# p0tx-001.net
KiCad netlist of a schematic drawn in EAGLE
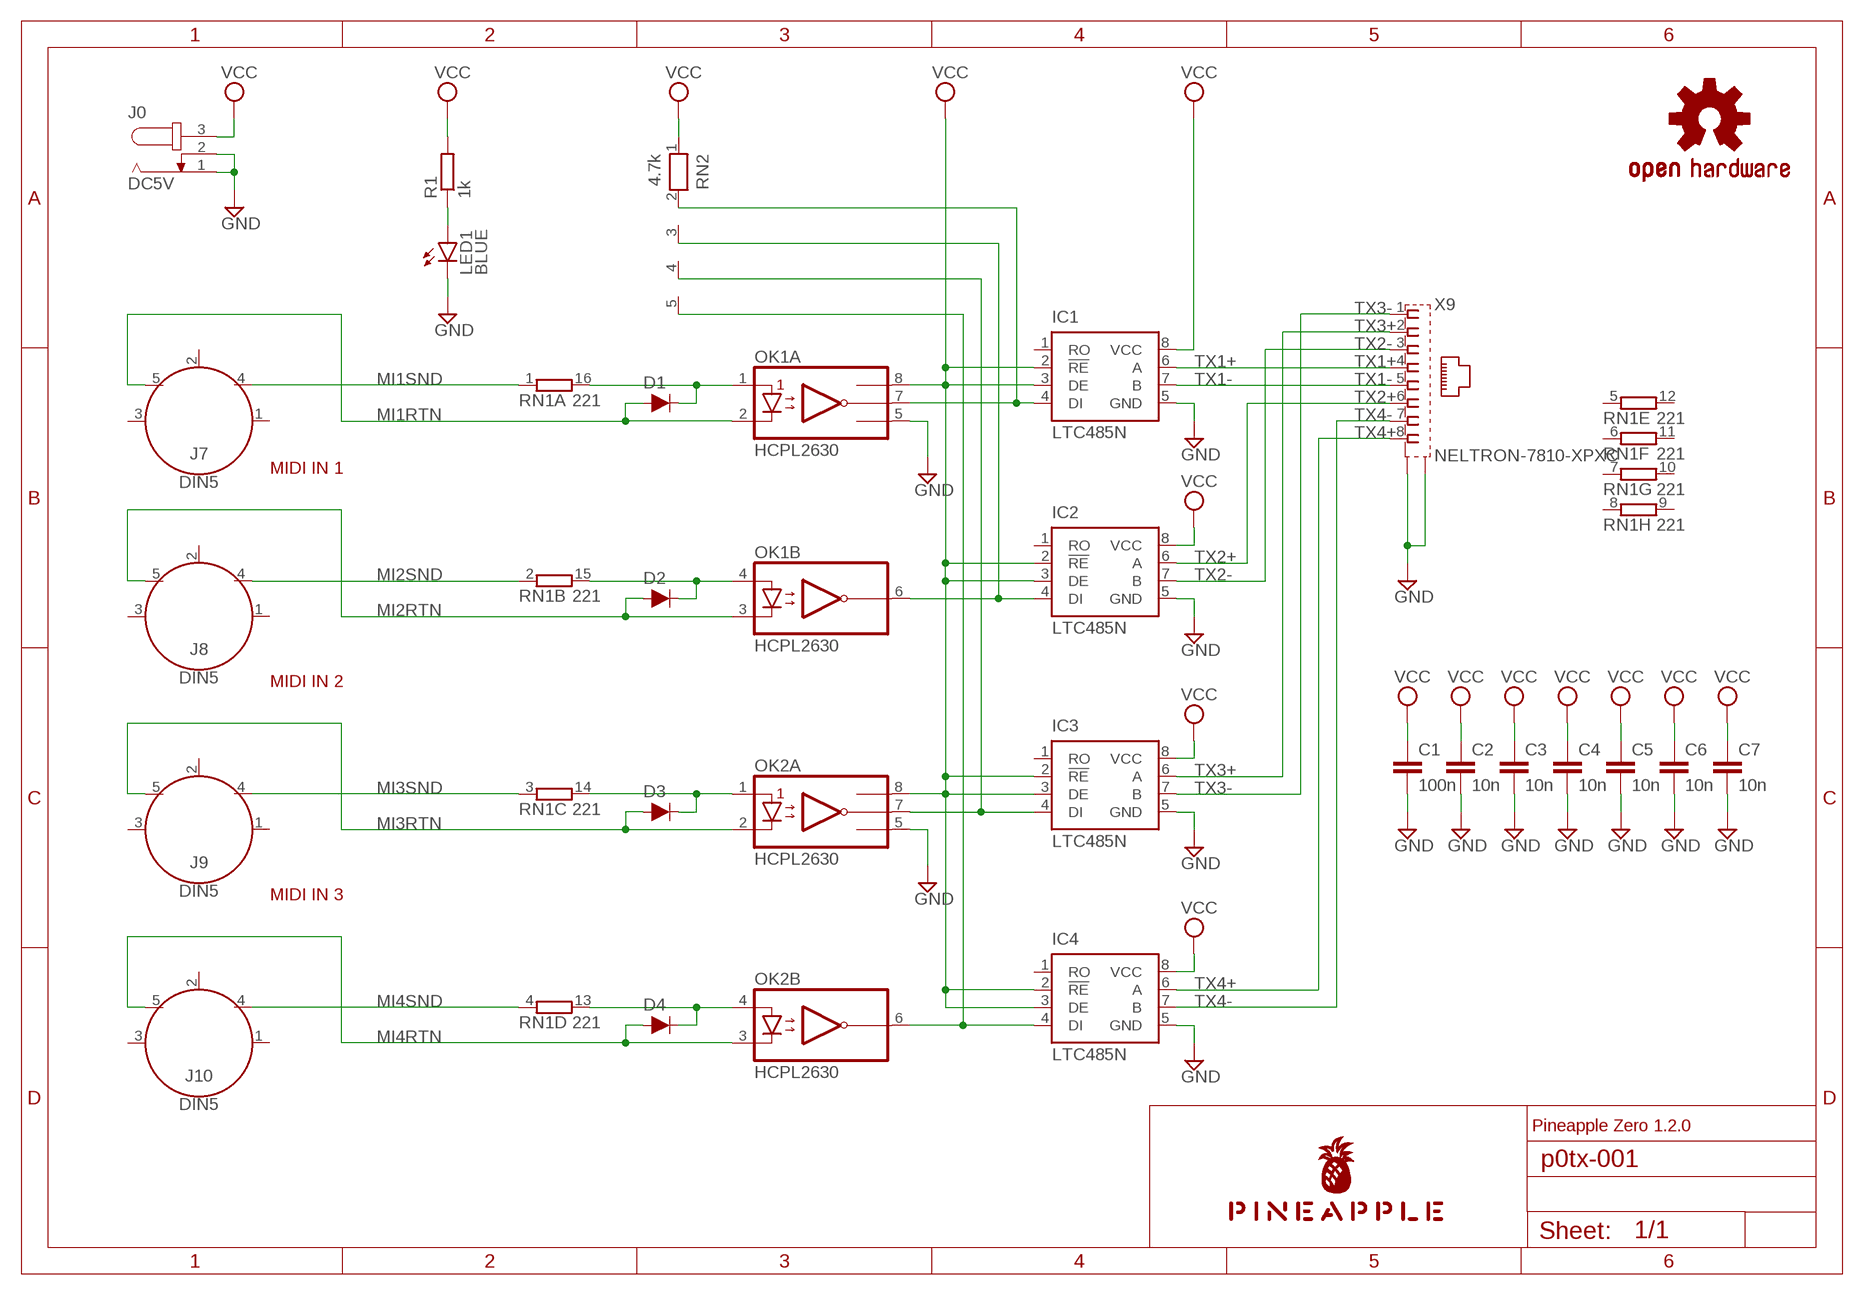
[diagram p0: schematic, sheet 1]

(export (version "E")
  (design (tool "Eeschema 10.0.6"))
  (components
    (comp (ref "C1")
      (value "100n")
      (footprint "eagle-import:C025-024X044")
      (libsource (lib "eagle-import") (part "C-EU025-024X044"))
    )
    (comp (ref "C2")
      (value "10n")
      (footprint "eagle-import:C025-024X044")
      (libsource (lib "eagle-import") (part "C-EU025-024X044"))
    )
    (comp (ref "C3")
      (value "10n")
      (footprint "eagle-import:C025-024X044")
      (libsource (lib "eagle-import") (part "C-EU025-024X044"))
    )
    (comp (ref "C4")
      (value "10n")
      (footprint "eagle-import:C025-024X044")
      (libsource (lib "eagle-import") (part "C-EU025-024X044"))
    )
    (comp (ref "C5")
      (value "10n")
      (footprint "eagle-import:C025-024X044")
      (libsource (lib "eagle-import") (part "C-EU025-024X044"))
    )
    (comp (ref "C6")
      (value "10n")
      (footprint "eagle-import:C025-024X044")
      (libsource (lib "eagle-import") (part "C-EU025-024X044"))
    )
    (comp (ref "C7")
      (value "10n")
      (footprint "eagle-import:C025-024X044")
      (libsource (lib "eagle-import") (part "C-EU025-024X044"))
    )
    (comp (ref "D1")
      (value "DIODE-1N4148")
      (footprint "eagle-import:DIODE-1N4148")
      (libsource (lib "eagle-import") (part "DIODE-1N4148"))
    )
    (comp (ref "D2")
      (value "DIODE-1N4148")
      (footprint "eagle-import:DIODE-1N4148")
      (libsource (lib "eagle-import") (part "DIODE-1N4148"))
    )
    (comp (ref "D3")
      (value "DIODE-1N4148")
      (footprint "eagle-import:DIODE-1N4148")
      (libsource (lib "eagle-import") (part "DIODE-1N4148"))
    )
    (comp (ref "D4")
      (value "DIODE-1N4148")
      (footprint "eagle-import:DIODE-1N4148")
      (libsource (lib "eagle-import") (part "DIODE-1N4148"))
    )
    (comp (ref "IC1")
      (value "LTC485N")
      (footprint "eagle-import:DIL08")
      (libsource (lib "eagle-import") (part "LTC485N"))
    )
    (comp (ref "IC2")
      (value "LTC485N")
      (footprint "eagle-import:DIL08")
      (libsource (lib "eagle-import") (part "LTC485N"))
    )
    (comp (ref "IC3")
      (value "LTC485N")
      (footprint "eagle-import:DIL08")
      (libsource (lib "eagle-import") (part "LTC485N"))
    )
    (comp (ref "IC4")
      (value "LTC485N")
      (footprint "eagle-import:DIL08")
      (libsource (lib "eagle-import") (part "LTC485N"))
    )
    (comp (ref "J0")
      (value "DC5V")
      (footprint "eagle-import:SPC4077")
      (libsource (lib "eagle-import") (part "JACK-PLUG0"))
    )
    (comp (ref "J7")
      (value "DIN5")
      (footprint "eagle-import:DIN5-RA-PTH")
      (libsource (lib "eagle-import") (part "DIN5"))
    )
    (comp (ref "J8")
      (value "DIN5")
      (footprint "eagle-import:DIN5-RA-PTH")
      (libsource (lib "eagle-import") (part "DIN5"))
    )
    (comp (ref "J9")
      (value "DIN5")
      (footprint "eagle-import:DIN5-RA-PTH")
      (libsource (lib "eagle-import") (part "DIN5"))
    )
    (comp (ref "J10")
      (value "DIN5")
      (footprint "eagle-import:DIN5-RA-PTH")
      (libsource (lib "eagle-import") (part "DIN5"))
    )
    (comp (ref "LED1")
      (value "BLUE")
      (footprint "eagle-import:LED3MM")
      (libsource (lib "eagle-import") (part "LED3MM"))
    )
    (comp (ref "LOGO1")
      (value "OSHW-LOGOS-COPPER")
      (footprint "eagle-import:OSHW-LOGO-S_COPPER")
      (libsource (lib "eagle-import") (part "OSHW-LOGOS-COPPER"))
    )
    (comp (ref "OK1")
      (value "HCPL2630")
      (footprint "eagle-import:DIL08")
      (fields (field (name "MF") "AGILENT TECHNOLOGIES") (field (name "MPN") "HCPL-2630-000E"))
      (libsource (lib "eagle-import") (part "HCPL2630"))
    )
    (comp (ref "OK2")
      (value "HCPL2630")
      (footprint "eagle-import:DIL08")
      (fields (field (name "MF") "AGILENT TECHNOLOGIES") (field (name "MPN") "HCPL-2630-000E"))
      (libsource (lib "eagle-import") (part "HCPL2630"))
    )
    (comp (ref "R1")
      (value "1k")
      (footprint "eagle-import:0204_5")
      (libsource (lib "eagle-import") (part "R-EU_0204/5"))
    )
    (comp (ref "RN1")
      (value "221")
      (footprint "eagle-import:DIL16")
      (libsource (lib "eagle-import") (part "8R-N"))
    )
    (comp (ref "RN2")
      (value "4.7k")
      (footprint "eagle-import:RN-5")
      (libsource (lib "eagle-import") (part "RN04"))
    )
    (comp (ref "U$1")
      (value "PINEAPPLE450")
      (footprint "eagle-import:PINEAPPLE450")
      (libsource (lib "eagle-import") (part "PINEAPPLE450"))
    )
    (comp (ref "X9")
      (value "NELTRON-7810-XPXC")
      (footprint "eagle-import:NELTRON-7810-XPXC-FOOTPRINT")
      (libsource (lib "eagle-import") (part "NELTRON-7810-XPXC"))
    )
  )
  (nets
    (net (code "1") (name "/MI1RTN") (class "Default")
      (node (ref "D1") (pin "A") (pinfunction "A_A") (pintype "passive"))
      (node (ref "J7") (pin "5") (pinfunction "5_5") (pintype "bidirectional"))
      (node (ref "OK1") (pin "2") (pinfunction "C1_2") (pintype "passive"))
    )
    (net (code "2") (name "/MI1SND") (class "Default")
      (node (ref "J7") (pin "4") (pinfunction "4_4") (pintype "bidirectional"))
      (node (ref "RN1") (pin "1") (pinfunction "1_1") (pintype "passive"))
    )
    (net (code "3") (name "/MI2RTN") (class "Default")
      (node (ref "D2") (pin "A") (pinfunction "A_A") (pintype "passive"))
      (node (ref "J8") (pin "5") (pinfunction "5_5") (pintype "bidirectional"))
      (node (ref "OK1") (pin "3") (pinfunction "C2_3") (pintype "passive"))
    )
    (net (code "4") (name "/MI2SND") (class "Default")
      (node (ref "J8") (pin "4") (pinfunction "4_4") (pintype "bidirectional"))
      (node (ref "RN1") (pin "2") (pinfunction "1_2") (pintype "passive"))
    )
    (net (code "5") (name "/MI3RTN") (class "Default")
      (node (ref "D3") (pin "A") (pinfunction "A_A") (pintype "passive"))
      (node (ref "J9") (pin "5") (pinfunction "5_5") (pintype "bidirectional"))
      (node (ref "OK2") (pin "2") (pinfunction "C1_2") (pintype "passive"))
    )
    (net (code "6") (name "/MI3SND") (class "Default")
      (node (ref "J9") (pin "4") (pinfunction "4_4") (pintype "bidirectional"))
      (node (ref "RN1") (pin "3") (pinfunction "1_3") (pintype "passive"))
    )
    (net (code "7") (name "/MI4RTN") (class "Default")
      (node (ref "D4") (pin "A") (pinfunction "A_A") (pintype "passive"))
      (node (ref "J10") (pin "5") (pinfunction "5_5") (pintype "bidirectional"))
      (node (ref "OK2") (pin "3") (pinfunction "C2_3") (pintype "passive"))
    )
    (net (code "8") (name "/MI4SND") (class "Default")
      (node (ref "J10") (pin "4") (pinfunction "4_4") (pintype "bidirectional"))
      (node (ref "RN1") (pin "4") (pinfunction "1_4") (pintype "passive"))
    )
    (net (code "9") (name "/TX1+") (class "Default")
      (node (ref "IC1") (pin "6") (pinfunction "A_6") (pintype "bidirectional"))
      (node (ref "X9") (pin "4") (pinfunction "4_4") (pintype "passive"))
    )
    (net (code "10") (name "/TX1-") (class "Default")
      (node (ref "IC1") (pin "7") (pinfunction "B_7") (pintype "bidirectional"))
      (node (ref "X9") (pin "5") (pinfunction "5_5") (pintype "passive"))
    )
    (net (code "11") (name "/TX2+") (class "Default")
      (node (ref "IC2") (pin "6") (pinfunction "A_6") (pintype "bidirectional"))
      (node (ref "X9") (pin "6") (pinfunction "6_6") (pintype "passive"))
    )
    (net (code "12") (name "/TX2-") (class "Default")
      (node (ref "IC2") (pin "7") (pinfunction "B_7") (pintype "bidirectional"))
      (node (ref "X9") (pin "3") (pinfunction "3_3") (pintype "passive"))
    )
    (net (code "13") (name "/TX3+") (class "Default")
      (node (ref "IC3") (pin "6") (pinfunction "A_6") (pintype "bidirectional"))
      (node (ref "X9") (pin "2") (pinfunction "2_2") (pintype "passive"))
    )
    (net (code "14") (name "/TX3-") (class "Default")
      (node (ref "IC3") (pin "7") (pinfunction "B_7") (pintype "bidirectional"))
      (node (ref "X9") (pin "1") (pinfunction "1_1") (pintype "passive"))
    )
    (net (code "15") (name "/TX4+") (class "Default")
      (node (ref "IC4") (pin "6") (pinfunction "A_6") (pintype "bidirectional"))
      (node (ref "X9") (pin "8") (pinfunction "8_8") (pintype "passive"))
    )
    (net (code "16") (name "/TX4-") (class "Default")
      (node (ref "IC4") (pin "7") (pinfunction "B_7") (pintype "bidirectional"))
      (node (ref "X9") (pin "7") (pinfunction "7_7") (pintype "passive"))
    )
    (net (code "17") (name "GND") (class "Default")
      (node (ref "C1") (pin "2") (pinfunction "2_2") (pintype "passive"))
      (node (ref "C2") (pin "2") (pinfunction "2_2") (pintype "passive"))
      (node (ref "C3") (pin "2") (pinfunction "2_2") (pintype "passive"))
      (node (ref "C4") (pin "2") (pinfunction "2_2") (pintype "passive"))
      (node (ref "C5") (pin "2") (pinfunction "2_2") (pintype "passive"))
      (node (ref "C6") (pin "2") (pinfunction "2_2") (pintype "passive"))
      (node (ref "C7") (pin "2") (pinfunction "2_2") (pintype "passive"))
      (node (ref "IC1") (pin "5") (pinfunction "GND_5") (pintype "input"))
      (node (ref "IC2") (pin "5") (pinfunction "GND_5") (pintype "input"))
      (node (ref "IC3") (pin "5") (pinfunction "GND_5") (pintype "input"))
      (node (ref "IC4") (pin "5") (pinfunction "GND_5") (pintype "input"))
      (node (ref "J0") (pin "1") (pinfunction "1_1") (pintype "passive"))
      (node (ref "J0") (pin "2") (pinfunction "2_2") (pintype "passive"))
      (node (ref "LED1") (pin "K") (pinfunction "C_K") (pintype "passive"))
      (node (ref "OK1") (pin "5") (pinfunction "GND_5") (pintype "passive"))
      (node (ref "OK2") (pin "5") (pinfunction "GND_5") (pintype "passive"))
      (node (ref "X9") (pin "S1") (pinfunction "S1_S1") (pintype "passive"))
      (node (ref "X9") (pin "S2") (pinfunction "S2_S2") (pintype "passive"))
    )
    (net (code "18") (name "Net-(IC1-DI)") (class "Default")
      (node (ref "IC1") (pin "4") (pinfunction "DI_4") (pintype "input"))
      (node (ref "OK1") (pin "7") (pinfunction "VO1_7") (pintype "passive"))
      (node (ref "RN2") (pin "2") (pinfunction "2_2") (pintype "passive"))
    )
    (net (code "19") (name "Net-(IC2-DI)") (class "Default")
      (node (ref "IC2") (pin "4") (pinfunction "DI_4") (pintype "input"))
      (node (ref "OK1") (pin "6") (pinfunction "VO2_6") (pintype "passive"))
      (node (ref "RN2") (pin "3") (pinfunction "3_3") (pintype "passive"))
    )
    (net (code "20") (name "Net-(IC3-DI)") (class "Default")
      (node (ref "IC3") (pin "4") (pinfunction "DI_4") (pintype "input"))
      (node (ref "OK2") (pin "7") (pinfunction "VO1_7") (pintype "passive"))
      (node (ref "RN2") (pin "4") (pinfunction "4_4") (pintype "passive"))
    )
    (net (code "21") (name "Net-(IC4-DI)") (class "Default")
      (node (ref "IC4") (pin "4") (pinfunction "DI_4") (pintype "input"))
      (node (ref "OK2") (pin "6") (pinfunction "VO2_6") (pintype "passive"))
      (node (ref "RN2") (pin "5") (pinfunction "5_5") (pintype "passive"))
    )
    (net (code "22") (name "Net-(LED1-PadA)") (class "Default")
      (node (ref "LED1") (pin "A") (pinfunction "A_A") (pintype "passive"))
      (node (ref "R1") (pin "1") (pinfunction "1_1") (pintype "passive"))
    )
    (net (code "23") (name "Net-(OK1A-A1)") (class "Default")
      (node (ref "D1") (pin "C") (pinfunction "C_C") (pintype "passive"))
      (node (ref "OK1") (pin "1") (pinfunction "A1_1") (pintype "passive"))
      (node (ref "RN1") (pin "16") (pinfunction "2_16") (pintype "passive"))
    )
    (net (code "24") (name "Net-(OK1B-A2)") (class "Default")
      (node (ref "D2") (pin "C") (pinfunction "C_C") (pintype "passive"))
      (node (ref "OK1") (pin "4") (pinfunction "A2_4") (pintype "passive"))
      (node (ref "RN1") (pin "15") (pinfunction "2_15") (pintype "passive"))
    )
    (net (code "25") (name "Net-(OK2A-A1)") (class "Default")
      (node (ref "D3") (pin "C") (pinfunction "C_C") (pintype "passive"))
      (node (ref "OK2") (pin "1") (pinfunction "A1_1") (pintype "passive"))
      (node (ref "RN1") (pin "14") (pinfunction "2_14") (pintype "passive"))
    )
    (net (code "26") (name "Net-(OK2B-A2)") (class "Default")
      (node (ref "D4") (pin "C") (pinfunction "C_C") (pintype "passive"))
      (node (ref "OK2") (pin "4") (pinfunction "A2_4") (pintype "passive"))
      (node (ref "RN1") (pin "13") (pinfunction "2_13") (pintype "passive"))
    )
    (net (code "27") (name "VCC") (class "Default")
      (node (ref "C1") (pin "1") (pinfunction "1_1") (pintype "passive"))
      (node (ref "C2") (pin "1") (pinfunction "1_1") (pintype "passive"))
      (node (ref "C3") (pin "1") (pinfunction "1_1") (pintype "passive"))
      (node (ref "C4") (pin "1") (pinfunction "1_1") (pintype "passive"))
      (node (ref "C5") (pin "1") (pinfunction "1_1") (pintype "passive"))
      (node (ref "C6") (pin "1") (pinfunction "1_1") (pintype "passive"))
      (node (ref "C7") (pin "1") (pinfunction "1_1") (pintype "passive"))
      (node (ref "IC1") (pin "2") (pinfunction "~{RE}_2") (pintype "input"))
      (node (ref "IC1") (pin "3") (pinfunction "DE_3") (pintype "input"))
      (node (ref "IC1") (pin "8") (pinfunction "VCC_8") (pintype "input"))
      (node (ref "IC2") (pin "2") (pinfunction "~{RE}_2") (pintype "input"))
      (node (ref "IC2") (pin "3") (pinfunction "DE_3") (pintype "input"))
      (node (ref "IC2") (pin "8") (pinfunction "VCC_8") (pintype "input"))
      (node (ref "IC3") (pin "2") (pinfunction "~{RE}_2") (pintype "input"))
      (node (ref "IC3") (pin "3") (pinfunction "DE_3") (pintype "input"))
      (node (ref "IC3") (pin "8") (pinfunction "VCC_8") (pintype "input"))
      (node (ref "IC4") (pin "2") (pinfunction "~{RE}_2") (pintype "input"))
      (node (ref "IC4") (pin "3") (pinfunction "DE_3") (pintype "input"))
      (node (ref "IC4") (pin "8") (pinfunction "VCC_8") (pintype "input"))
      (node (ref "J0") (pin "3") (pinfunction "3_3") (pintype "passive"))
      (node (ref "OK1") (pin "8") (pinfunction "VCC_8") (pintype "passive"))
      (node (ref "OK2") (pin "8") (pinfunction "VCC_8") (pintype "passive"))
      (node (ref "R1") (pin "2") (pinfunction "2_2") (pintype "passive"))
      (node (ref "RN2") (pin "1") (pinfunction "1_1") (pintype "passive"))
    )
    (net (code "28") (name "unconnected-(IC1-RO-Pad1)") (class "Default")
      (node (ref "IC1") (pin "1") (pinfunction "RO_1") (pintype "output"))
    )
    (net (code "29") (name "unconnected-(IC2-RO-Pad1)") (class "Default")
      (node (ref "IC2") (pin "1") (pinfunction "RO_1") (pintype "output"))
    )
    (net (code "30") (name "unconnected-(IC3-RO-Pad1)") (class "Default")
      (node (ref "IC3") (pin "1") (pinfunction "RO_1") (pintype "output"))
    )
    (net (code "31") (name "unconnected-(IC4-RO-Pad1)") (class "Default")
      (node (ref "IC4") (pin "1") (pinfunction "RO_1") (pintype "output"))
    )
    (net (code "32") (name "unconnected-(J7-Pad1)") (class "Default")
      (node (ref "J7") (pin "1") (pinfunction "1_1") (pintype "bidirectional"))
    )
    (net (code "33") (name "unconnected-(J7-Pad2)") (class "Default")
      (node (ref "J7") (pin "2") (pinfunction "2_2") (pintype "bidirectional"))
    )
    (net (code "34") (name "unconnected-(J7-Pad3)") (class "Default")
      (node (ref "J7") (pin "3") (pinfunction "3_3") (pintype "bidirectional"))
    )
    (net (code "35") (name "unconnected-(J8-Pad1)") (class "Default")
      (node (ref "J8") (pin "1") (pinfunction "1_1") (pintype "bidirectional"))
    )
    (net (code "36") (name "unconnected-(J8-Pad2)") (class "Default")
      (node (ref "J8") (pin "2") (pinfunction "2_2") (pintype "bidirectional"))
    )
    (net (code "37") (name "unconnected-(J8-Pad3)") (class "Default")
      (node (ref "J8") (pin "3") (pinfunction "3_3") (pintype "bidirectional"))
    )
    (net (code "38") (name "unconnected-(J9-Pad1)") (class "Default")
      (node (ref "J9") (pin "1") (pinfunction "1_1") (pintype "bidirectional"))
    )
    (net (code "39") (name "unconnected-(J9-Pad2)") (class "Default")
      (node (ref "J9") (pin "2") (pinfunction "2_2") (pintype "bidirectional"))
    )
    (net (code "40") (name "unconnected-(J9-Pad3)") (class "Default")
      (node (ref "J9") (pin "3") (pinfunction "3_3") (pintype "bidirectional"))
    )
    (net (code "41") (name "unconnected-(J10-Pad1)") (class "Default")
      (node (ref "J10") (pin "1") (pinfunction "1_1") (pintype "bidirectional"))
    )
    (net (code "42") (name "unconnected-(J10-Pad2)") (class "Default")
      (node (ref "J10") (pin "2") (pinfunction "2_2") (pintype "bidirectional"))
    )
    (net (code "43") (name "unconnected-(J10-Pad3)") (class "Default")
      (node (ref "J10") (pin "3") (pinfunction "3_3") (pintype "bidirectional"))
    )
    (net (code "44") (name "unconnected-(RN1E-1-Pad5)") (class "Default")
      (node (ref "RN1") (pin "5") (pinfunction "1_5") (pintype "passive"))
    )
    (net (code "45") (name "unconnected-(RN1E-2-Pad12)") (class "Default")
      (node (ref "RN1") (pin "12") (pinfunction "2_12") (pintype "passive"))
    )
    (net (code "46") (name "unconnected-(RN1F-1-Pad6)") (class "Default")
      (node (ref "RN1") (pin "6") (pinfunction "1_6") (pintype "passive"))
    )
    (net (code "47") (name "unconnected-(RN1F-2-Pad11)") (class "Default")
      (node (ref "RN1") (pin "11") (pinfunction "2_11") (pintype "passive"))
    )
    (net (code "48") (name "unconnected-(RN1G-1-Pad7)") (class "Default")
      (node (ref "RN1") (pin "7") (pinfunction "1_7") (pintype "passive"))
    )
    (net (code "49") (name "unconnected-(RN1G-2-Pad10)") (class "Default")
      (node (ref "RN1") (pin "10") (pinfunction "2_10") (pintype "passive"))
    )
    (net (code "50") (name "unconnected-(RN1H-1-Pad8)") (class "Default")
      (node (ref "RN1") (pin "8") (pinfunction "1_8") (pintype "passive"))
    )
    (net (code "51") (name "unconnected-(RN1H-2-Pad9)") (class "Default")
      (node (ref "RN1") (pin "9") (pinfunction "2_9") (pintype "passive"))
    )
  )
)
